# SoundSystem-V0_2_1.net
KiCad netlist of a schematic drawn in EasyEDA
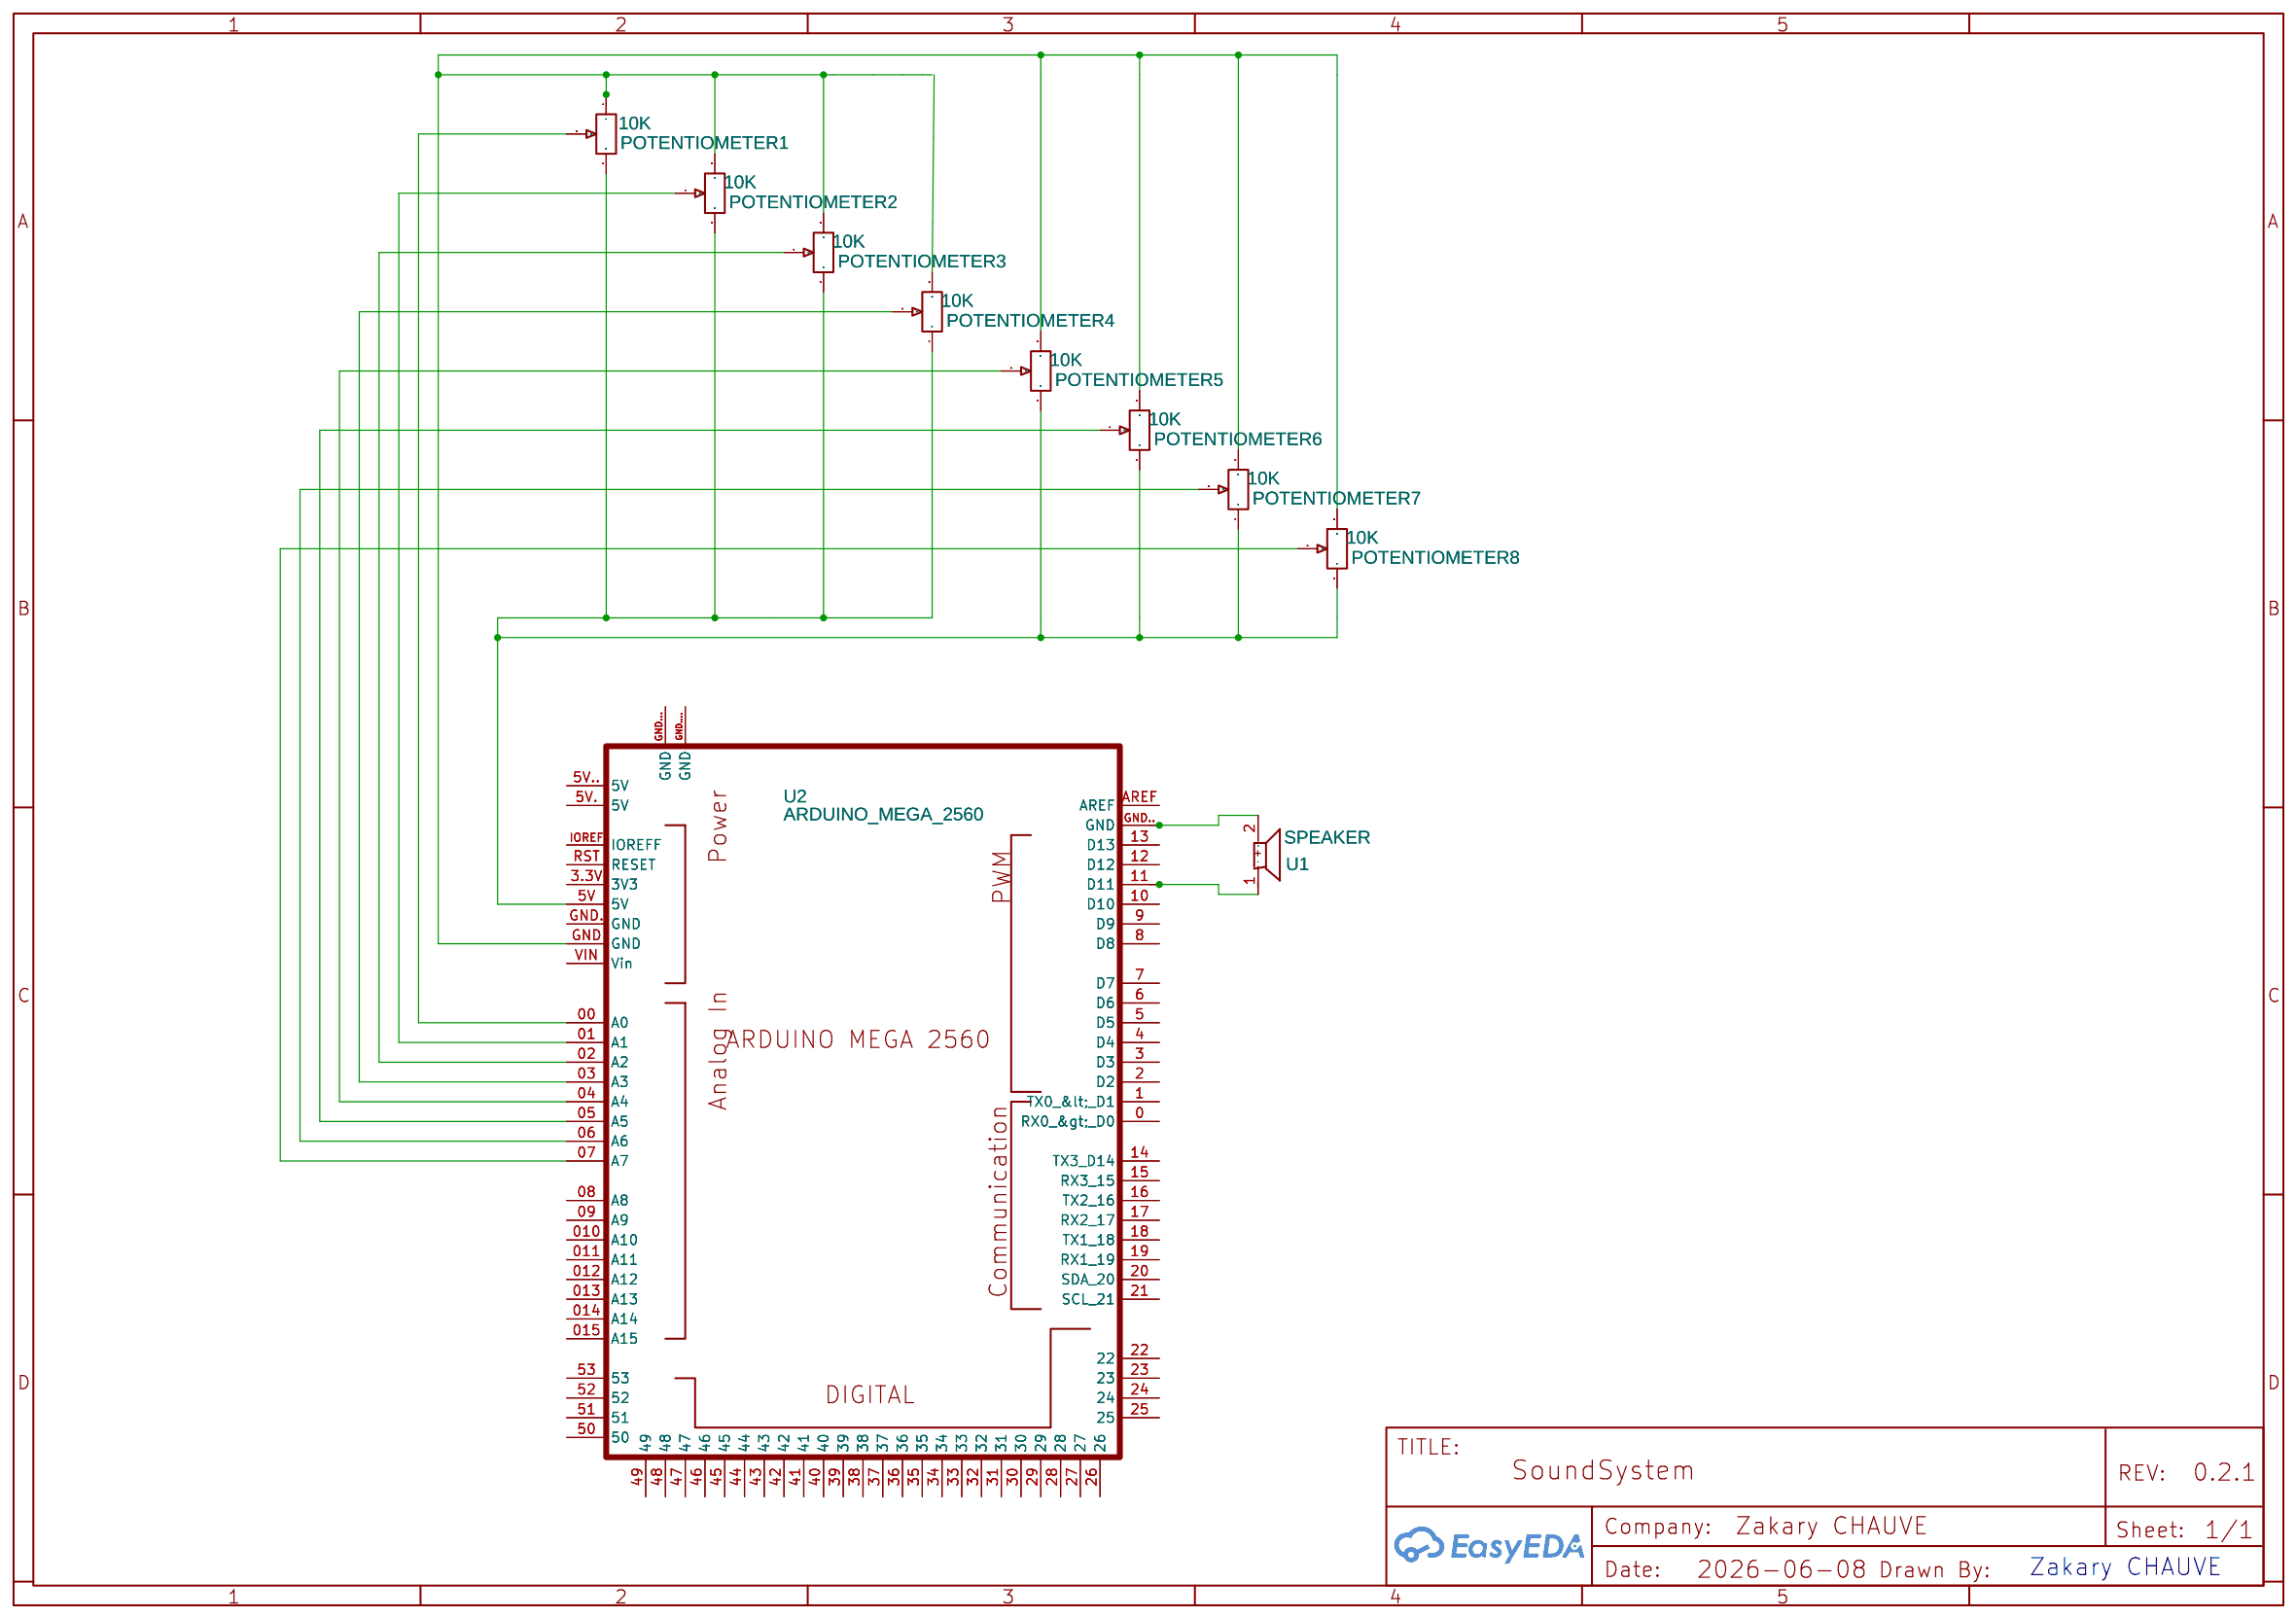
[diagram p0: schematic sheet]

(export (version "E")
  (design (tool "Eeschema 10.0.6"))
  (components
    (comp (ref "POTENTIOMETER1")
      (value "10K")
      (fields
        (field (name "Manufacturer Part") "Potentiometer WH160-1-104")
        (field (name "Manufacturer") "JML")
      )
      (libsource (lib "") (part "Pot-10k-Potentiometer_1"))
    )
    (comp (ref "POTENTIOMETER2")
      (value "10K")
      (fields
        (field (name "Manufacturer Part") "Potentiometer WH160-1-104")
        (field (name "Manufacturer") "JML")
      )
      (libsource (lib "") (part "Pot-10k-Potentiometer"))
    )
    (comp (ref "POTENTIOMETER3")
      (value "10K")
      (fields
        (field (name "Manufacturer Part") "Potentiometer WH160-1-104")
        (field (name "Manufacturer") "JML")
      )
      (libsource (lib "") (part "Pot-10k-Potentiometer"))
    )
    (comp (ref "POTENTIOMETER4")
      (value "10K")
      (fields
        (field (name "Manufacturer Part") "Potentiometer WH160-1-104")
        (field (name "Manufacturer") "JML")
      )
      (libsource (lib "") (part "Pot-10k-Potentiometer"))
    )
    (comp (ref "POTENTIOMETER5")
      (value "10K")
      (fields
        (field (name "Manufacturer Part") "Potentiometer WH160-1-104")
        (field (name "Manufacturer") "JML")
      )
      (libsource (lib "") (part "Pot-10k-Potentiometer"))
    )
    (comp (ref "POTENTIOMETER6")
      (value "10K")
      (fields
        (field (name "Manufacturer Part") "Potentiometer WH160-1-104")
        (field (name "Manufacturer") "JML")
      )
      (libsource (lib "") (part "Pot-10k-Potentiometer"))
    )
    (comp (ref "POTENTIOMETER7")
      (value "10K")
      (fields
        (field (name "Manufacturer Part") "Potentiometer WH160-1-104")
        (field (name "Manufacturer") "JML")
      )
      (libsource (lib "") (part "Pot-10k-Potentiometer"))
    )
    (comp (ref "POTENTIOMETER8")
      (value "10K")
      (fields
        (field (name "Manufacturer Part") "Potentiometer WH160-1-104")
        (field (name "Manufacturer") "JML")
      )
      (libsource (lib "") (part "Pot-10k-Potentiometer"))
    )
    (comp (ref "U1") (value "SPEAKER") (libsource (lib "") (part "speaker")))
    (comp (ref "U2") (value "ARDUINO_MEGA_2560") (libsource (lib "") (part "ARDUINO_MEGA_2560 COPY")))
  )
  (nets
    (net (code "1") (name "Net-(POTENTIOMETER1-Pad1)") (class "Default")
      (node (ref "POTENTIOMETER1") (pin "1") (pinfunction "1_1") (pintype "input"))
      (node (ref "POTENTIOMETER2") (pin "3") (pinfunction "3_3") (pintype "input"))
      (node (ref "POTENTIOMETER3") (pin "3") (pinfunction "3_3") (pintype "input"))
      (node (ref "POTENTIOMETER5") (pin "3") (pinfunction "3_3") (pintype "input"))
      (node (ref "POTENTIOMETER6") (pin "3") (pinfunction "3_3") (pintype "input"))
      (node (ref "POTENTIOMETER7") (pin "3") (pinfunction "3_3") (pintype "input"))
      (node (ref "POTENTIOMETER8") (pin "3") (pinfunction "3_3") (pintype "input"))
      (node (ref "U2") (pin "GND") (pinfunction "GND_GND") (pintype "unspecified"))
    )
    (net (code "2") (name "Net-(POTENTIOMETER1-Pad3)") (class "Default")
      (node (ref "POTENTIOMETER1") (pin "3") (pinfunction "3_3") (pintype "input"))
      (node (ref "POTENTIOMETER2") (pin "1") (pinfunction "1_1") (pintype "input"))
      (node (ref "POTENTIOMETER3") (pin "1") (pinfunction "1_1") (pintype "input"))
      (node (ref "POTENTIOMETER4") (pin "1") (pinfunction "1_1") (pintype "input"))
      (node (ref "POTENTIOMETER5") (pin "1") (pinfunction "1_1") (pintype "input"))
      (node (ref "POTENTIOMETER6") (pin "1") (pinfunction "1_1") (pintype "input"))
      (node (ref "POTENTIOMETER7") (pin "1") (pinfunction "1_1") (pintype "input"))
      (node (ref "POTENTIOMETER8") (pin "1") (pinfunction "1_1") (pintype "input"))
      (node (ref "U2") (pin "5V") (pinfunction "5V_5V") (pintype "unspecified"))
    )
    (net (code "3") (name "Net-(U1-+)") (class "Default")
      (node (ref "U1") (pin "2") (pinfunction "+_2") (pintype "unspecified"))
      (node (ref "U2") (pin "GND..") (pinfunction "GND_GND..") (pintype "unspecified"))
    )
    (net (code "4") (name "Net-(U1--)") (class "Default")
      (node (ref "U1") (pin "1") (pinfunction "-_1") (pintype "unspecified"))
      (node (ref "U2") (pin "11") (pinfunction "D11_11") (pintype "unspecified"))
    )
    (net (code "5") (name "Net-(U2-A0)") (class "Default")
      (node (ref "POTENTIOMETER1") (pin "2") (pinfunction "2_2") (pintype "input"))
      (node (ref "U2") (pin "00") (pinfunction "A0_00") (pintype "unspecified"))
    )
    (net (code "6") (name "Net-(U2-A1)") (class "Default")
      (node (ref "POTENTIOMETER2") (pin "2") (pinfunction "2_2") (pintype "input"))
      (node (ref "U2") (pin "01") (pinfunction "A1_01") (pintype "unspecified"))
    )
    (net (code "7") (name "Net-(U2-A2)") (class "Default")
      (node (ref "POTENTIOMETER3") (pin "2") (pinfunction "2_2") (pintype "input"))
      (node (ref "U2") (pin "02") (pinfunction "A2_02") (pintype "unspecified"))
    )
    (net (code "8") (name "Net-(U2-A3)") (class "Default")
      (node (ref "POTENTIOMETER4") (pin "2") (pinfunction "2_2") (pintype "input"))
      (node (ref "U2") (pin "03") (pinfunction "A3_03") (pintype "unspecified"))
    )
    (net (code "9") (name "Net-(U2-A4)") (class "Default")
      (node (ref "POTENTIOMETER5") (pin "2") (pinfunction "2_2") (pintype "input"))
      (node (ref "U2") (pin "04") (pinfunction "A4_04") (pintype "unspecified"))
    )
    (net (code "10") (name "Net-(U2-A5)") (class "Default")
      (node (ref "POTENTIOMETER6") (pin "2") (pinfunction "2_2") (pintype "input"))
      (node (ref "U2") (pin "05") (pinfunction "A5_05") (pintype "unspecified"))
    )
    (net (code "11") (name "Net-(U2-A6)") (class "Default")
      (node (ref "POTENTIOMETER7") (pin "2") (pinfunction "2_2") (pintype "input"))
      (node (ref "U2") (pin "06") (pinfunction "A6_06") (pintype "unspecified"))
    )
    (net (code "12") (name "Net-(U2-A7)") (class "Default")
      (node (ref "POTENTIOMETER8") (pin "2") (pinfunction "2_2") (pintype "input"))
      (node (ref "U2") (pin "07") (pinfunction "A7_07") (pintype "unspecified"))
    )
    (net (code "13") (name "unconnected-(POTENTIOMETER4-Pad3)") (class "Default")
      (node (ref "POTENTIOMETER4") (pin "3") (pinfunction "3_3") (pintype "input"))
    )
    (net (code "14") (name "unconnected-(U2-3V3-Pad3.3V)") (class "Default")
      (node (ref "U2") (pin "3.3V") (pinfunction "3V3_3.3V") (pintype "unspecified"))
    )
    (net (code "15") (name "unconnected-(U2-5V-Pad5V.)") (class "Default")
      (node (ref "U2") (pin "5V.") (pinfunction "5V_5V.") (pintype "unspecified"))
    )
    (net (code "16") (name "unconnected-(U2-5V-Pad5V..)") (class "Default")
      (node (ref "U2") (pin "5V..") (pinfunction "5V_5V..") (pintype "unspecified"))
    )
    (net (code "17") (name "unconnected-(U2-A8-Pad08)") (class "Default")
      (node (ref "U2") (pin "08") (pinfunction "A8_08") (pintype "unspecified"))
    )
    (net (code "18") (name "unconnected-(U2-A9-Pad09)") (class "Default")
      (node (ref "U2") (pin "09") (pinfunction "A9_09") (pintype "unspecified"))
    )
    (net (code "19") (name "unconnected-(U2-A10-Pad010)") (class "Default")
      (node (ref "U2") (pin "010") (pinfunction "A10_010") (pintype "unspecified"))
    )
    (net (code "20") (name "unconnected-(U2-A11-Pad011)") (class "Default")
      (node (ref "U2") (pin "011") (pinfunction "A11_011") (pintype "unspecified"))
    )
    (net (code "21") (name "unconnected-(U2-A12-Pad012)") (class "Default")
      (node (ref "U2") (pin "012") (pinfunction "A12_012") (pintype "unspecified"))
    )
    (net (code "22") (name "unconnected-(U2-A13-Pad013)") (class "Default")
      (node (ref "U2") (pin "013") (pinfunction "A13_013") (pintype "unspecified"))
    )
    (net (code "23") (name "unconnected-(U2-A14-Pad014)") (class "Default")
      (node (ref "U2") (pin "014") (pinfunction "A14_014") (pintype "unspecified"))
    )
    (net (code "24") (name "unconnected-(U2-A15-Pad015)") (class "Default")
      (node (ref "U2") (pin "015") (pinfunction "A15_015") (pintype "unspecified"))
    )
    (net (code "25") (name "unconnected-(U2-D2-Pad2)") (class "Default")
      (node (ref "U2") (pin "2") (pinfunction "D2_2") (pintype "unspecified"))
    )
    (net (code "26") (name "unconnected-(U2-D3-Pad3)") (class "Default")
      (node (ref "U2") (pin "3") (pinfunction "D3_3") (pintype "unspecified"))
    )
    (net (code "27") (name "unconnected-(U2-D4-Pad4)") (class "Default")
      (node (ref "U2") (pin "4") (pinfunction "D4_4") (pintype "unspecified"))
    )
    (net (code "28") (name "unconnected-(U2-D5-Pad5)") (class "Default")
      (node (ref "U2") (pin "5") (pinfunction "D5_5") (pintype "unspecified"))
    )
    (net (code "29") (name "unconnected-(U2-D6-Pad6)") (class "Default")
      (node (ref "U2") (pin "6") (pinfunction "D6_6") (pintype "unspecified"))
    )
    (net (code "30") (name "unconnected-(U2-D7-Pad7)") (class "Default")
      (node (ref "U2") (pin "7") (pinfunction "D7_7") (pintype "unspecified"))
    )
    (net (code "31") (name "unconnected-(U2-D8-Pad8)") (class "Default")
      (node (ref "U2") (pin "8") (pinfunction "D8_8") (pintype "unspecified"))
    )
    (net (code "32") (name "unconnected-(U2-D9-Pad9)") (class "Default")
      (node (ref "U2") (pin "9") (pinfunction "D9_9") (pintype "unspecified"))
    )
    (net (code "33") (name "unconnected-(U2-D10-Pad10)") (class "Default")
      (node (ref "U2") (pin "10") (pinfunction "D10_10") (pintype "unspecified"))
    )
    (net (code "34") (name "unconnected-(U2-D12-Pad12)") (class "Default")
      (node (ref "U2") (pin "12") (pinfunction "D12_12") (pintype "unspecified"))
    )
    (net (code "35") (name "unconnected-(U2-D13-Pad13)") (class "Default")
      (node (ref "U2") (pin "13") (pinfunction "D13_13") (pintype "unspecified"))
    )
    (net (code "36") (name "unconnected-(U2-GND-PadGND.)") (class "Default")
      (node (ref "U2") (pin "GND.") (pinfunction "GND_GND.") (pintype "unspecified"))
    )
    (net (code "37") (name "unconnected-(U2-GND-PadGND...)") (class "Default")
      (node (ref "U2") (pin "GND...") (pinfunction "GND_GND...") (pintype "unspecified"))
    )
    (net (code "38") (name "unconnected-(U2-GND-PadGND....)") (class "Default")
      (node (ref "U2") (pin "GND....") (pinfunction "GND_GND....") (pintype "unspecified"))
    )
    (net (code "39") (name "unconnected-(U2-IOREFF-PadIOREF)") (class "Default")
      (node (ref "U2") (pin "IOREF") (pinfunction "IOREFF_IOREF") (pintype "unspecified"))
    )
    (net (code "40") (name "unconnected-(U2-Pad22)") (class "Default")
      (node (ref "U2") (pin "22") (pinfunction "22_22") (pintype "unspecified"))
    )
    (net (code "41") (name "unconnected-(U2-Pad23)") (class "Default")
      (node (ref "U2") (pin "23") (pinfunction "23_23") (pintype "unspecified"))
    )
    (net (code "42") (name "unconnected-(U2-Pad24)") (class "Default")
      (node (ref "U2") (pin "24") (pinfunction "24_24") (pintype "unspecified"))
    )
    (net (code "43") (name "unconnected-(U2-Pad25)") (class "Default")
      (node (ref "U2") (pin "25") (pinfunction "25_25") (pintype "unspecified"))
    )
    (net (code "44") (name "unconnected-(U2-Pad26)") (class "Default")
      (node (ref "U2") (pin "26") (pinfunction "26_26") (pintype "unspecified"))
    )
    (net (code "45") (name "unconnected-(U2-Pad27)") (class "Default")
      (node (ref "U2") (pin "27") (pinfunction "27_27") (pintype "unspecified"))
    )
    (net (code "46") (name "unconnected-(U2-Pad28)") (class "Default")
      (node (ref "U2") (pin "28") (pinfunction "28_28") (pintype "unspecified"))
    )
    (net (code "47") (name "unconnected-(U2-Pad29)") (class "Default")
      (node (ref "U2") (pin "29") (pinfunction "29_29") (pintype "unspecified"))
    )
    (net (code "48") (name "unconnected-(U2-Pad30)") (class "Default")
      (node (ref "U2") (pin "30") (pinfunction "30_30") (pintype "unspecified"))
    )
    (net (code "49") (name "unconnected-(U2-Pad31)") (class "Default")
      (node (ref "U2") (pin "31") (pinfunction "31_31") (pintype "unspecified"))
    )
    (net (code "50") (name "unconnected-(U2-Pad32)") (class "Default")
      (node (ref "U2") (pin "32") (pinfunction "32_32") (pintype "unspecified"))
    )
    (net (code "51") (name "unconnected-(U2-Pad33)") (class "Default")
      (node (ref "U2") (pin "33") (pinfunction "33_33") (pintype "unspecified"))
    )
    (net (code "52") (name "unconnected-(U2-Pad34)") (class "Default")
      (node (ref "U2") (pin "34") (pinfunction "34_34") (pintype "unspecified"))
    )
    (net (code "53") (name "unconnected-(U2-Pad35)") (class "Default")
      (node (ref "U2") (pin "35") (pinfunction "35_35") (pintype "unspecified"))
    )
    (net (code "54") (name "unconnected-(U2-Pad36)") (class "Default")
      (node (ref "U2") (pin "36") (pinfunction "36_36") (pintype "unspecified"))
    )
    (net (code "55") (name "unconnected-(U2-Pad37)") (class "Default")
      (node (ref "U2") (pin "37") (pinfunction "37_37") (pintype "unspecified"))
    )
    (net (code "56") (name "unconnected-(U2-Pad38)") (class "Default")
      (node (ref "U2") (pin "38") (pinfunction "38_38") (pintype "unspecified"))
    )
    (net (code "57") (name "unconnected-(U2-Pad39)") (class "Default")
      (node (ref "U2") (pin "39") (pinfunction "39_39") (pintype "unspecified"))
    )
    (net (code "58") (name "unconnected-(U2-Pad40)") (class "Default")
      (node (ref "U2") (pin "40") (pinfunction "40_40") (pintype "unspecified"))
    )
    (net (code "59") (name "unconnected-(U2-Pad41)") (class "Default")
      (node (ref "U2") (pin "41") (pinfunction "41_41") (pintype "unspecified"))
    )
    (net (code "60") (name "unconnected-(U2-Pad42)") (class "Default")
      (node (ref "U2") (pin "42") (pinfunction "42_42") (pintype "unspecified"))
    )
    (net (code "61") (name "unconnected-(U2-Pad43)") (class "Default")
      (node (ref "U2") (pin "43") (pinfunction "43_43") (pintype "unspecified"))
    )
    (net (code "62") (name "unconnected-(U2-Pad44)") (class "Default")
      (node (ref "U2") (pin "44") (pinfunction "44_44") (pintype "unspecified"))
    )
    (net (code "63") (name "unconnected-(U2-Pad45)") (class "Default")
      (node (ref "U2") (pin "45") (pinfunction "45_45") (pintype "unspecified"))
    )
    (net (code "64") (name "unconnected-(U2-Pad46)") (class "Default")
      (node (ref "U2") (pin "46") (pinfunction "46_46") (pintype "unspecified"))
    )
    (net (code "65") (name "unconnected-(U2-Pad47)") (class "Default")
      (node (ref "U2") (pin "47") (pinfunction "47_47") (pintype "unspecified"))
    )
    (net (code "66") (name "unconnected-(U2-Pad48)") (class "Default")
      (node (ref "U2") (pin "48") (pinfunction "48_48") (pintype "unspecified"))
    )
    (net (code "67") (name "unconnected-(U2-Pad49)") (class "Default")
      (node (ref "U2") (pin "49") (pinfunction "49_49") (pintype "unspecified"))
    )
    (net (code "68") (name "unconnected-(U2-Pad50)") (class "Default")
      (node (ref "U2") (pin "50") (pinfunction "50_50") (pintype "unspecified"))
    )
    (net (code "69") (name "unconnected-(U2-Pad51)") (class "Default")
      (node (ref "U2") (pin "51") (pinfunction "51_51") (pintype "unspecified"))
    )
    (net (code "70") (name "unconnected-(U2-Pad52)") (class "Default")
      (node (ref "U2") (pin "52") (pinfunction "52_52") (pintype "unspecified"))
    )
    (net (code "71") (name "unconnected-(U2-Pad53)") (class "Default")
      (node (ref "U2") (pin "53") (pinfunction "53_53") (pintype "unspecified"))
    )
    (net (code "72") (name "unconnected-(U2-PadAREF)") (class "Default")
      (node (ref "U2") (pin "AREF") (pinfunction "AREF_AREF") (pintype "unspecified"))
    )
    (net (code "73") (name "unconnected-(U2-RESET-PadRST)") (class "Default")
      (node (ref "U2") (pin "RST") (pinfunction "RESET_RST") (pintype "unspecified"))
    )
    (net (code "74") (name "unconnected-(U2-RX0_&gt;_D0-Pad0)") (class "Default")
      (node (ref "U2") (pin "0") (pinfunction "RX0_&gt;_D0_0") (pintype "unspecified"))
    )
    (net (code "75") (name "unconnected-(U2-RX1_19-Pad19)") (class "Default")
      (node (ref "U2") (pin "19") (pinfunction "RX1_19_19") (pintype "unspecified"))
    )
    (net (code "76") (name "unconnected-(U2-RX2_17-Pad17)") (class "Default")
      (node (ref "U2") (pin "17") (pinfunction "RX2_17_17") (pintype "unspecified"))
    )
    (net (code "77") (name "unconnected-(U2-RX3_15-Pad15)") (class "Default")
      (node (ref "U2") (pin "15") (pinfunction "RX3_15_15") (pintype "unspecified"))
    )
    (net (code "78") (name "unconnected-(U2-SCL_21-Pad21)") (class "Default")
      (node (ref "U2") (pin "21") (pinfunction "SCL_21_21") (pintype "unspecified"))
    )
    (net (code "79") (name "unconnected-(U2-SDA_20-Pad20)") (class "Default")
      (node (ref "U2") (pin "20") (pinfunction "SDA_20_20") (pintype "unspecified"))
    )
    (net (code "80") (name "unconnected-(U2-TX0_&lt;_D1-Pad1)") (class "Default")
      (node (ref "U2") (pin "1") (pinfunction "TX0_&lt;_D1_1") (pintype "unspecified"))
    )
    (net (code "81") (name "unconnected-(U2-TX1_18-Pad18)") (class "Default")
      (node (ref "U2") (pin "18") (pinfunction "TX1_18_18") (pintype "unspecified"))
    )
    (net (code "82") (name "unconnected-(U2-TX2_16-Pad16)") (class "Default")
      (node (ref "U2") (pin "16") (pinfunction "TX2_16_16") (pintype "unspecified"))
    )
    (net (code "83") (name "unconnected-(U2-TX3_D14-Pad14)") (class "Default")
      (node (ref "U2") (pin "14") (pinfunction "TX3_D14_14") (pintype "unspecified"))
    )
    (net (code "84") (name "unconnected-(U2-Vin-PadVIN)") (class "Default")
      (node (ref "U2") (pin "VIN") (pinfunction "Vin_VIN") (pintype "unspecified"))
    )
  )
)
